# cpu-module.net
KiCad netlist of a schematic drawn in EAGLE
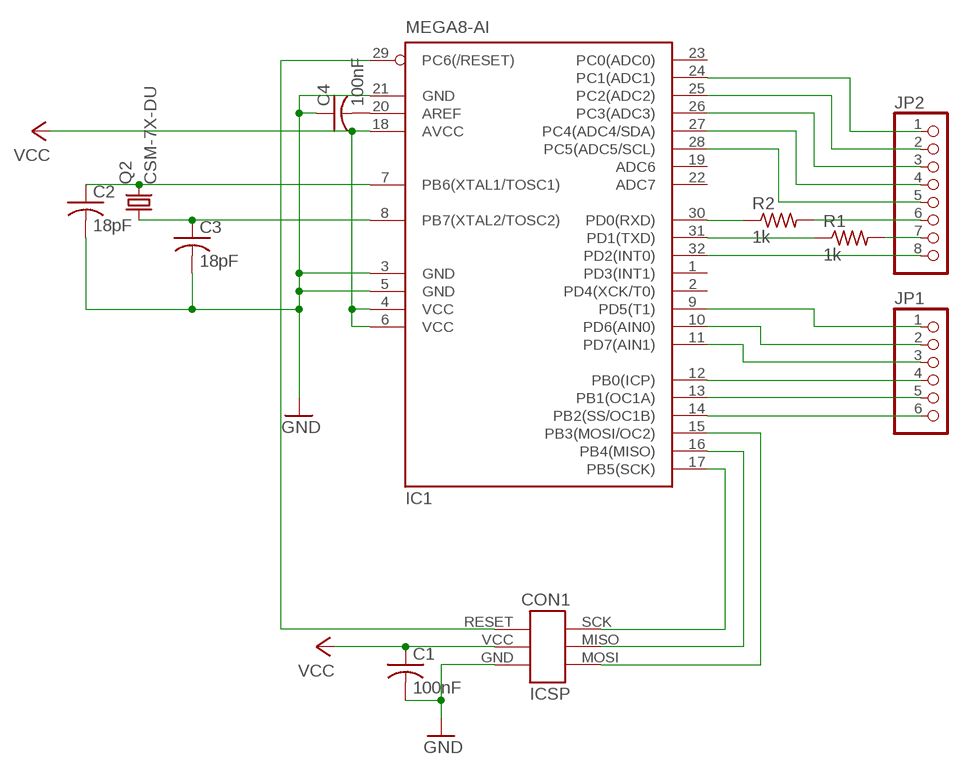
[diagram p0: schematic, sheet 1]

(export (version "E")
  (design (tool "Eeschema 10.0.6"))
  (components
    (comp (ref "C1")
      (value "100nF")
      (footprint "eagle-import:C0603K")
      (libsource (lib "eagle-import") (part "C-USC0603K"))
    )
    (comp (ref "C2")
      (value "18pF")
      (footprint "eagle-import:C0805")
      (libsource (lib "eagle-import") (part "C-USC0805"))
    )
    (comp (ref "C3")
      (value "18pF")
      (footprint "eagle-import:C0805")
      (libsource (lib "eagle-import") (part "C-USC0805"))
    )
    (comp (ref "C4")
      (value "100nF")
      (footprint "eagle-import:C0603K")
      (libsource (lib "eagle-import") (part "C-USC0603K"))
    )
    (comp (ref "CON1")
      (value "ICSP-HEADER")
      (footprint "eagle-import:ICSP-HEADER")
      (libsource (lib "eagle-import") (part "ICSP-HEADER"))
    )
    (comp (ref "IC1")
      (value "MEGA8-AI")
      (footprint "eagle-import:TQFP32-08")
      (fields (field (name "MPN") "ATMEGA8-16AU"))
      (libsource (lib "eagle-import") (part "MEGA8-AI"))
    )
    (comp (ref "JP1")
      (value "PINHD-1X6B")
      (footprint "eagle-import:1X06-BIG")
      (libsource (lib "eagle-import") (part "PINHD-1X6B"))
    )
    (comp (ref "JP2")
      (value "PINHD-1X8BIG")
      (footprint "eagle-import:1X08-BIG")
      (libsource (lib "eagle-import") (part "PINHD-1X8BIG"))
    )
    (comp (ref "Q2")
      (value "CSM-7X-DU")
      (footprint "eagle-import:CSM-7X-DU")
      (libsource (lib "eagle-import") (part "CSM-7X-DU"))
    )
    (comp (ref "R1")
      (value "1k")
      (footprint "eagle-import:R0603")
      (libsource (lib "eagle-import") (part "R-US_R0603"))
    )
    (comp (ref "R2")
      (value "1k")
      (footprint "eagle-import:R0603")
      (libsource (lib "eagle-import") (part "R-US_R0603"))
    )
  )
  (nets
    (net (code "1") (name "GND") (class "Default")
      (node (ref "C1") (pin "2") (pinfunction "2_2") (pintype "passive"))
      (node (ref "C2") (pin "2") (pinfunction "2_2") (pintype "passive"))
      (node (ref "C3") (pin "2") (pinfunction "2_2") (pintype "passive"))
      (node (ref "C4") (pin "1") (pinfunction "1_1") (pintype "passive"))
      (node (ref "CON1") (pin "GND") (pinfunction "GND_GND") (pintype "bidirectional"))
      (node (ref "IC1") (pin "21") (pinfunction "GND_21") (pintype "power_in"))
      (node (ref "IC1") (pin "3") (pinfunction "GND_3") (pintype "power_in"))
      (node (ref "IC1") (pin "5") (pinfunction "GND_5") (pintype "power_in"))
    )
    (net (code "2") (name "Net-(IC1-AREF)") (class "Default")
      (node (ref "C4") (pin "2") (pinfunction "2_2") (pintype "passive"))
      (node (ref "IC1") (pin "20") (pinfunction "AREF_20") (pintype "passive"))
    )
    (net (code "3") (name "Net-(IC1-PB0(ICP))") (class "Default")
      (node (ref "IC1") (pin "12") (pinfunction "PB0(ICP)_12") (pintype "bidirectional"))
      (node (ref "JP1") (pin "4") (pinfunction "4_4") (pintype "passive"))
    )
    (net (code "4") (name "Net-(IC1-PB1(OC1A))") (class "Default")
      (node (ref "IC1") (pin "13") (pinfunction "PB1(OC1A)_13") (pintype "bidirectional"))
      (node (ref "JP1") (pin "5") (pinfunction "5_5") (pintype "passive"))
    )
    (net (code "5") (name "Net-(IC1-PB2(SS{slash}OC1B))") (class "Default")
      (node (ref "IC1") (pin "14") (pinfunction "PB2(SS/OC1B)_14") (pintype "bidirectional"))
      (node (ref "JP1") (pin "6") (pinfunction "6_6") (pintype "passive"))
    )
    (net (code "6") (name "Net-(IC1-PB3(MOSI{slash}OC2))") (class "Default")
      (node (ref "CON1") (pin "MOSI") (pinfunction "MOSI_MOSI") (pintype "bidirectional"))
      (node (ref "IC1") (pin "15") (pinfunction "PB3(MOSI/OC2)_15") (pintype "bidirectional"))
    )
    (net (code "7") (name "Net-(IC1-PB4(MISO))") (class "Default")
      (node (ref "CON1") (pin "MISO") (pinfunction "MISO_MISO") (pintype "bidirectional"))
      (node (ref "IC1") (pin "16") (pinfunction "PB4(MISO)_16") (pintype "bidirectional"))
    )
    (net (code "8") (name "Net-(IC1-PB5(SCK))") (class "Default")
      (node (ref "CON1") (pin "SCK") (pinfunction "SCK_SCK") (pintype "bidirectional"))
      (node (ref "IC1") (pin "17") (pinfunction "PB5(SCK)_17") (pintype "bidirectional"))
    )
    (net (code "9") (name "Net-(IC1-PB6(XTAL1{slash}TOSC1))") (class "Default")
      (node (ref "C2") (pin "1") (pinfunction "1_1") (pintype "passive"))
      (node (ref "IC1") (pin "7") (pinfunction "PB6(XTAL1/TOSC1)_7") (pintype "bidirectional"))
      (node (ref "Q2") (pin "2") (pinfunction "2_2") (pintype "passive"))
    )
    (net (code "10") (name "Net-(IC1-PB7(XTAL2{slash}TOSC2))") (class "Default")
      (node (ref "C3") (pin "1") (pinfunction "1_1") (pintype "passive"))
      (node (ref "IC1") (pin "8") (pinfunction "PB7(XTAL2/TOSC2)_8") (pintype "bidirectional"))
      (node (ref "Q2") (pin "1") (pinfunction "1_1") (pintype "passive"))
    )
    (net (code "11") (name "Net-(IC1-PC1(ADC1))") (class "Default")
      (node (ref "IC1") (pin "24") (pinfunction "PC1(ADC1)_24") (pintype "bidirectional"))
      (node (ref "JP2") (pin "1") (pinfunction "1_1") (pintype "passive"))
    )
    (net (code "12") (name "Net-(IC1-PC2(ADC2))") (class "Default")
      (node (ref "IC1") (pin "25") (pinfunction "PC2(ADC2)_25") (pintype "bidirectional"))
      (node (ref "JP2") (pin "2") (pinfunction "2_2") (pintype "passive"))
    )
    (net (code "13") (name "Net-(IC1-PC3(ADC3))") (class "Default")
      (node (ref "IC1") (pin "26") (pinfunction "PC3(ADC3)_26") (pintype "bidirectional"))
      (node (ref "JP2") (pin "3") (pinfunction "3_3") (pintype "passive"))
    )
    (net (code "14") (name "Net-(IC1-PC4(ADC4{slash}SDA))") (class "Default")
      (node (ref "IC1") (pin "27") (pinfunction "PC4(ADC4/SDA)_27") (pintype "bidirectional"))
      (node (ref "JP2") (pin "4") (pinfunction "4_4") (pintype "passive"))
    )
    (net (code "15") (name "Net-(IC1-PC5(ADC5{slash}SCL))") (class "Default")
      (node (ref "IC1") (pin "28") (pinfunction "PC5(ADC5/SCL)_28") (pintype "bidirectional"))
      (node (ref "JP2") (pin "5") (pinfunction "5_5") (pintype "passive"))
    )
    (net (code "16") (name "Net-(IC1-PC6({slash}RESET))") (class "Default")
      (node (ref "CON1") (pin "RESET") (pinfunction "RESET_RESET") (pintype "bidirectional"))
      (node (ref "IC1") (pin "29") (pinfunction "PC6(/RESET)_29") (pintype "bidirectional"))
    )
    (net (code "17") (name "Net-(IC1-PD0(RXD))") (class "Default")
      (node (ref "IC1") (pin "30") (pinfunction "PD0(RXD)_30") (pintype "bidirectional"))
      (node (ref "R2") (pin "1") (pinfunction "1_1") (pintype "passive"))
    )
    (net (code "18") (name "Net-(IC1-PD1(TXD))") (class "Default")
      (node (ref "IC1") (pin "31") (pinfunction "PD1(TXD)_31") (pintype "bidirectional"))
      (node (ref "R1") (pin "1") (pinfunction "1_1") (pintype "passive"))
    )
    (net (code "19") (name "Net-(IC1-PD2(INT0))") (class "Default")
      (node (ref "IC1") (pin "32") (pinfunction "PD2(INT0)_32") (pintype "bidirectional"))
      (node (ref "JP2") (pin "8") (pinfunction "8_8") (pintype "passive"))
    )
    (net (code "20") (name "Net-(IC1-PD5(T1))") (class "Default")
      (node (ref "IC1") (pin "9") (pinfunction "PD5(T1)_9") (pintype "bidirectional"))
      (node (ref "JP1") (pin "1") (pinfunction "1_1") (pintype "passive"))
    )
    (net (code "21") (name "Net-(IC1-PD6(AIN0))") (class "Default")
      (node (ref "IC1") (pin "10") (pinfunction "PD6(AIN0)_10") (pintype "bidirectional"))
      (node (ref "JP1") (pin "2") (pinfunction "2_2") (pintype "passive"))
    )
    (net (code "22") (name "Net-(IC1-PD7(AIN1))") (class "Default")
      (node (ref "IC1") (pin "11") (pinfunction "PD7(AIN1)_11") (pintype "bidirectional"))
      (node (ref "JP1") (pin "3") (pinfunction "3_3") (pintype "passive"))
    )
    (net (code "23") (name "Net-(JP2-Pad6)") (class "Default")
      (node (ref "JP2") (pin "6") (pinfunction "6_6") (pintype "passive"))
      (node (ref "R2") (pin "2") (pinfunction "2_2") (pintype "passive"))
    )
    (net (code "24") (name "Net-(JP2-Pad7)") (class "Default")
      (node (ref "JP2") (pin "7") (pinfunction "7_7") (pintype "passive"))
      (node (ref "R1") (pin "2") (pinfunction "2_2") (pintype "passive"))
    )
    (net (code "25") (name "VCC") (class "Default")
      (node (ref "C1") (pin "1") (pinfunction "1_1") (pintype "passive"))
      (node (ref "CON1") (pin "VCC") (pinfunction "+5V_VCC") (pintype "bidirectional"))
      (node (ref "IC1") (pin "18") (pinfunction "AVCC_18") (pintype "power_in"))
      (node (ref "IC1") (pin "4") (pinfunction "VCC_4") (pintype "power_in"))
      (node (ref "IC1") (pin "6") (pinfunction "VCC_6") (pintype "power_in"))
    )
    (net (code "26") (name "unconnected-(IC1-ADC6-Pad19)") (class "Default")
      (node (ref "IC1") (pin "19") (pinfunction "ADC6_19") (pintype "bidirectional"))
    )
    (net (code "27") (name "unconnected-(IC1-ADC7-Pad22)") (class "Default")
      (node (ref "IC1") (pin "22") (pinfunction "ADC7_22") (pintype "bidirectional"))
    )
    (net (code "28") (name "unconnected-(IC1-PC0(ADC0)-Pad23)") (class "Default")
      (node (ref "IC1") (pin "23") (pinfunction "PC0(ADC0)_23") (pintype "bidirectional"))
    )
    (net (code "29") (name "unconnected-(IC1-PD3(INT1)-Pad1)") (class "Default")
      (node (ref "IC1") (pin "1") (pinfunction "PD3(INT1)_1") (pintype "bidirectional"))
    )
    (net (code "30") (name "unconnected-(IC1-PD4(XCK{slash}T0)-Pad2)") (class "Default")
      (node (ref "IC1") (pin "2") (pinfunction "PD4(XCK/T0)_2") (pintype "bidirectional"))
    )
  )
)
